# sensor4.net
KiCad netlist of a schematic drawn in EAGLE
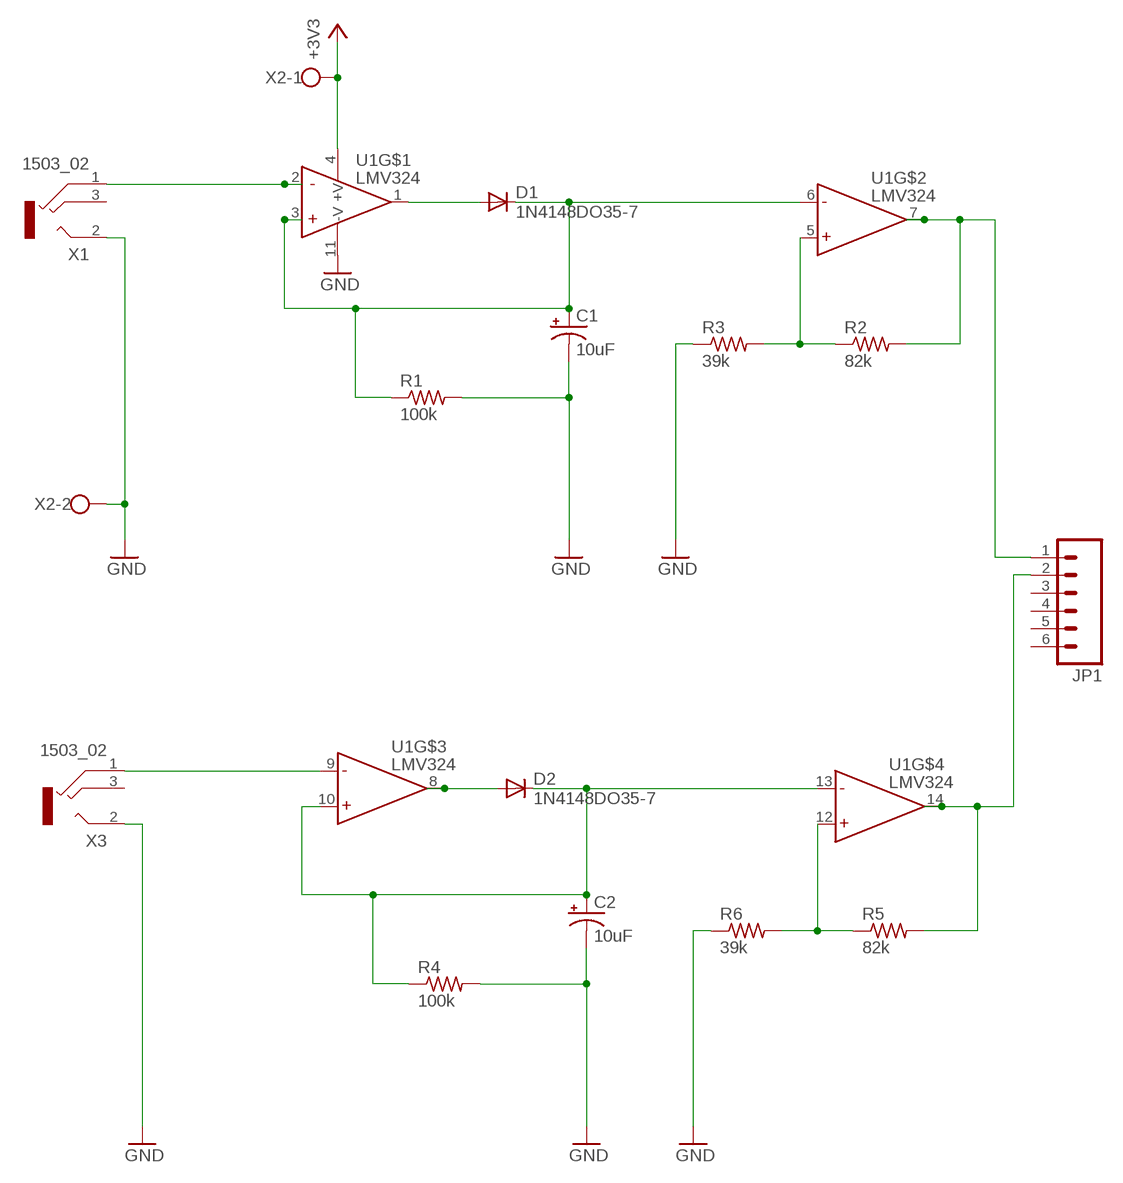
[diagram p0: schematic, sheet 1]

(export (version "E")
  (design (tool "Eeschema 10.0.6"))
  (components
    (comp (ref "C1")
      (value "10uF")
      (footprint "eagle-import:E2,5-5")
      (libsource (lib "eagle-import") (part "CPOL-USE2.5-5"))
    )
    (comp (ref "C2")
      (value "10uF")
      (footprint "eagle-import:E2,5-5")
      (libsource (lib "eagle-import") (part "CPOL-USE2.5-5"))
    )
    (comp (ref "D1")
      (value "1N4148DO35-7")
      (footprint "eagle-import:DO35-7")
      (libsource (lib "eagle-import") (part "1N4148DO35-7"))
    )
    (comp (ref "D2")
      (value "1N4148DO35-7")
      (footprint "eagle-import:DO35-7")
      (libsource (lib "eagle-import") (part "1N4148DO35-7"))
    )
    (comp (ref "JP1")
      (value "M06SIP")
      (footprint "eagle-import:1X06")
      (libsource (lib "eagle-import") (part "M06SIP"))
    )
    (comp (ref "R1")
      (value "100k")
      (footprint "eagle-import:0207_10")
      (libsource (lib "eagle-import") (part "R-US_0207/10"))
    )
    (comp (ref "R2")
      (value "82k")
      (footprint "eagle-import:0207_10")
      (libsource (lib "eagle-import") (part "R-US_0207/10"))
    )
    (comp (ref "R3")
      (value "39k")
      (footprint "eagle-import:0207_10")
      (libsource (lib "eagle-import") (part "R-US_0207/10"))
    )
    (comp (ref "R4")
      (value "100k")
      (footprint "eagle-import:0207_10")
      (libsource (lib "eagle-import") (part "R-US_0207/10"))
    )
    (comp (ref "R5")
      (value "82k")
      (footprint "eagle-import:0207_10")
      (libsource (lib "eagle-import") (part "R-US_0207/10"))
    )
    (comp (ref "R6")
      (value "39k")
      (footprint "eagle-import:0207_10")
      (libsource (lib "eagle-import") (part "R-US_0207/10"))
    )
    (comp (ref "U1")
      (value "LMV324")
      (footprint "eagle-import:SO014")
      (libsource (lib "eagle-import") (part "LMV324"))
    )
    (comp (ref "X1")
      (value "1503_02")
      (footprint "eagle-import:1503_02")
      (libsource (lib "eagle-import") (part "1503_02"))
    )
    (comp (ref "X2")
      (value "W237-102")
      (footprint "eagle-import:W237-102")
      (fields (field (name "MPN") "237-102"))
      (libsource (lib "eagle-import") (part "W237-102"))
    )
    (comp (ref "X3")
      (value "1503_02")
      (footprint "eagle-import:1503_02")
      (libsource (lib "eagle-import") (part "1503_02"))
    )
  )
  (nets
    (net (code "1") (name "+3V3") (class "Default")
      (node (ref "U1") (pin "4") (pinfunction "+V_4") (pintype "power_in"))
      (node (ref "X2") (pin "1") (pinfunction "KL_1") (pintype "passive"))
    )
    (net (code "2") (name "GND") (class "Default")
      (node (ref "C1") (pin "-") (pinfunction "-_-") (pintype "passive"))
      (node (ref "C2") (pin "-") (pinfunction "-_-") (pintype "passive"))
      (node (ref "R1") (pin "2") (pinfunction "2_2") (pintype "passive"))
      (node (ref "R3") (pin "1") (pinfunction "1_1") (pintype "passive"))
      (node (ref "R4") (pin "2") (pinfunction "2_2") (pintype "passive"))
      (node (ref "R6") (pin "1") (pinfunction "1_1") (pintype "passive"))
      (node (ref "U1") (pin "11") (pinfunction "-V_11") (pintype "power_in"))
      (node (ref "X1") (pin "2") (pinfunction "2_2") (pintype "passive"))
      (node (ref "X2") (pin "2") (pinfunction "KL_2") (pintype "passive"))
      (node (ref "X3") (pin "2") (pinfunction "2_2") (pintype "passive"))
    )
    (net (code "3") (name "Net-(U1A-+IN)") (class "Default")
      (node (ref "C1") (pin "+") (pinfunction "+_+") (pintype "passive"))
      (node (ref "D1") (pin "C") (pinfunction "C_C") (pintype "passive"))
      (node (ref "R1") (pin "1") (pinfunction "1_1") (pintype "passive"))
      (node (ref "U1") (pin "3") (pinfunction "+IN_3") (pintype "input"))
      (node (ref "U1") (pin "6") (pinfunction "-IN_6") (pintype "power_in"))
    )
    (net (code "4") (name "Net-(U1A--IN)") (class "Default")
      (node (ref "U1") (pin "2") (pinfunction "-IN_2") (pintype "input"))
      (node (ref "X1") (pin "1") (pinfunction "1_1") (pintype "passive"))
    )
    (net (code "5") (name "Net-(U1A-OUT)") (class "Default")
      (node (ref "D1") (pin "A") (pinfunction "A_A") (pintype "passive"))
      (node (ref "U1") (pin "1") (pinfunction "OUT_1") (pintype "output"))
    )
    (net (code "6") (name "Net-(U1B-+IN)") (class "Default")
      (node (ref "R2") (pin "1") (pinfunction "1_1") (pintype "passive"))
      (node (ref "R3") (pin "2") (pinfunction "2_2") (pintype "passive"))
      (node (ref "U1") (pin "5") (pinfunction "+IN_5") (pintype "power_in"))
    )
    (net (code "7") (name "Net-(U1B-OUT)") (class "Default")
      (node (ref "JP1") (pin "1") (pinfunction "1_1") (pintype "passive"))
      (node (ref "R2") (pin "2") (pinfunction "2_2") (pintype "passive"))
      (node (ref "U1") (pin "7") (pinfunction "OUT_7") (pintype "power_in"))
    )
    (net (code "8") (name "Net-(U1C-+IN)") (class "Default")
      (node (ref "C2") (pin "+") (pinfunction "+_+") (pintype "passive"))
      (node (ref "D2") (pin "C") (pinfunction "C_C") (pintype "passive"))
      (node (ref "R4") (pin "1") (pinfunction "1_1") (pintype "passive"))
      (node (ref "U1") (pin "10") (pinfunction "+IN_10") (pintype "power_in"))
      (node (ref "U1") (pin "13") (pinfunction "-IN_13") (pintype "power_in"))
    )
    (net (code "9") (name "Net-(U1C--IN)") (class "Default")
      (node (ref "U1") (pin "9") (pinfunction "-IN_9") (pintype "power_in"))
      (node (ref "X3") (pin "1") (pinfunction "1_1") (pintype "passive"))
    )
    (net (code "10") (name "Net-(U1C-OUT)") (class "Default")
      (node (ref "D2") (pin "A") (pinfunction "A_A") (pintype "passive"))
      (node (ref "U1") (pin "8") (pinfunction "OUT_8") (pintype "power_in"))
    )
    (net (code "11") (name "Net-(U1D-+IN)") (class "Default")
      (node (ref "R5") (pin "1") (pinfunction "1_1") (pintype "passive"))
      (node (ref "R6") (pin "2") (pinfunction "2_2") (pintype "passive"))
      (node (ref "U1") (pin "12") (pinfunction "+IN_12") (pintype "power_in"))
    )
    (net (code "12") (name "Net-(U1D-OUT)") (class "Default")
      (node (ref "JP1") (pin "2") (pinfunction "2_2") (pintype "passive"))
      (node (ref "R5") (pin "2") (pinfunction "2_2") (pintype "passive"))
      (node (ref "U1") (pin "14") (pinfunction "OUT_14") (pintype "power_in"))
    )
    (net (code "13") (name "unconnected-(JP1-Pad3)") (class "Default")
      (node (ref "JP1") (pin "3") (pinfunction "3_3") (pintype "passive"))
    )
    (net (code "14") (name "unconnected-(JP1-Pad4)") (class "Default")
      (node (ref "JP1") (pin "4") (pinfunction "4_4") (pintype "passive"))
    )
    (net (code "15") (name "unconnected-(JP1-Pad5)") (class "Default")
      (node (ref "JP1") (pin "5") (pinfunction "5_5") (pintype "passive"))
    )
    (net (code "16") (name "unconnected-(JP1-Pad6)") (class "Default")
      (node (ref "JP1") (pin "6") (pinfunction "6_6") (pintype "passive"))
    )
    (net (code "17") (name "unconnected-(X1-2-Pad2@2)") (class "Default")
      (node (ref "X1") (pin "2@2") (pinfunction "2_2@2") (pintype "passive"))
    )
    (net (code "18") (name "unconnected-(X1-Pad3)") (class "Default")
      (node (ref "X1") (pin "3") (pinfunction "3_3") (pintype "passive"))
    )
    (net (code "19") (name "unconnected-(X3-2-Pad2@2)") (class "Default")
      (node (ref "X3") (pin "2@2") (pinfunction "2_2@2") (pintype "passive"))
    )
    (net (code "20") (name "unconnected-(X3-Pad3)") (class "Default")
      (node (ref "X3") (pin "3") (pinfunction "3_3") (pintype "passive"))
    )
  )
)
